# BusPirate-ultra-testboard_v1_0.net
KiCad netlist of a schematic drawn in EAGLE
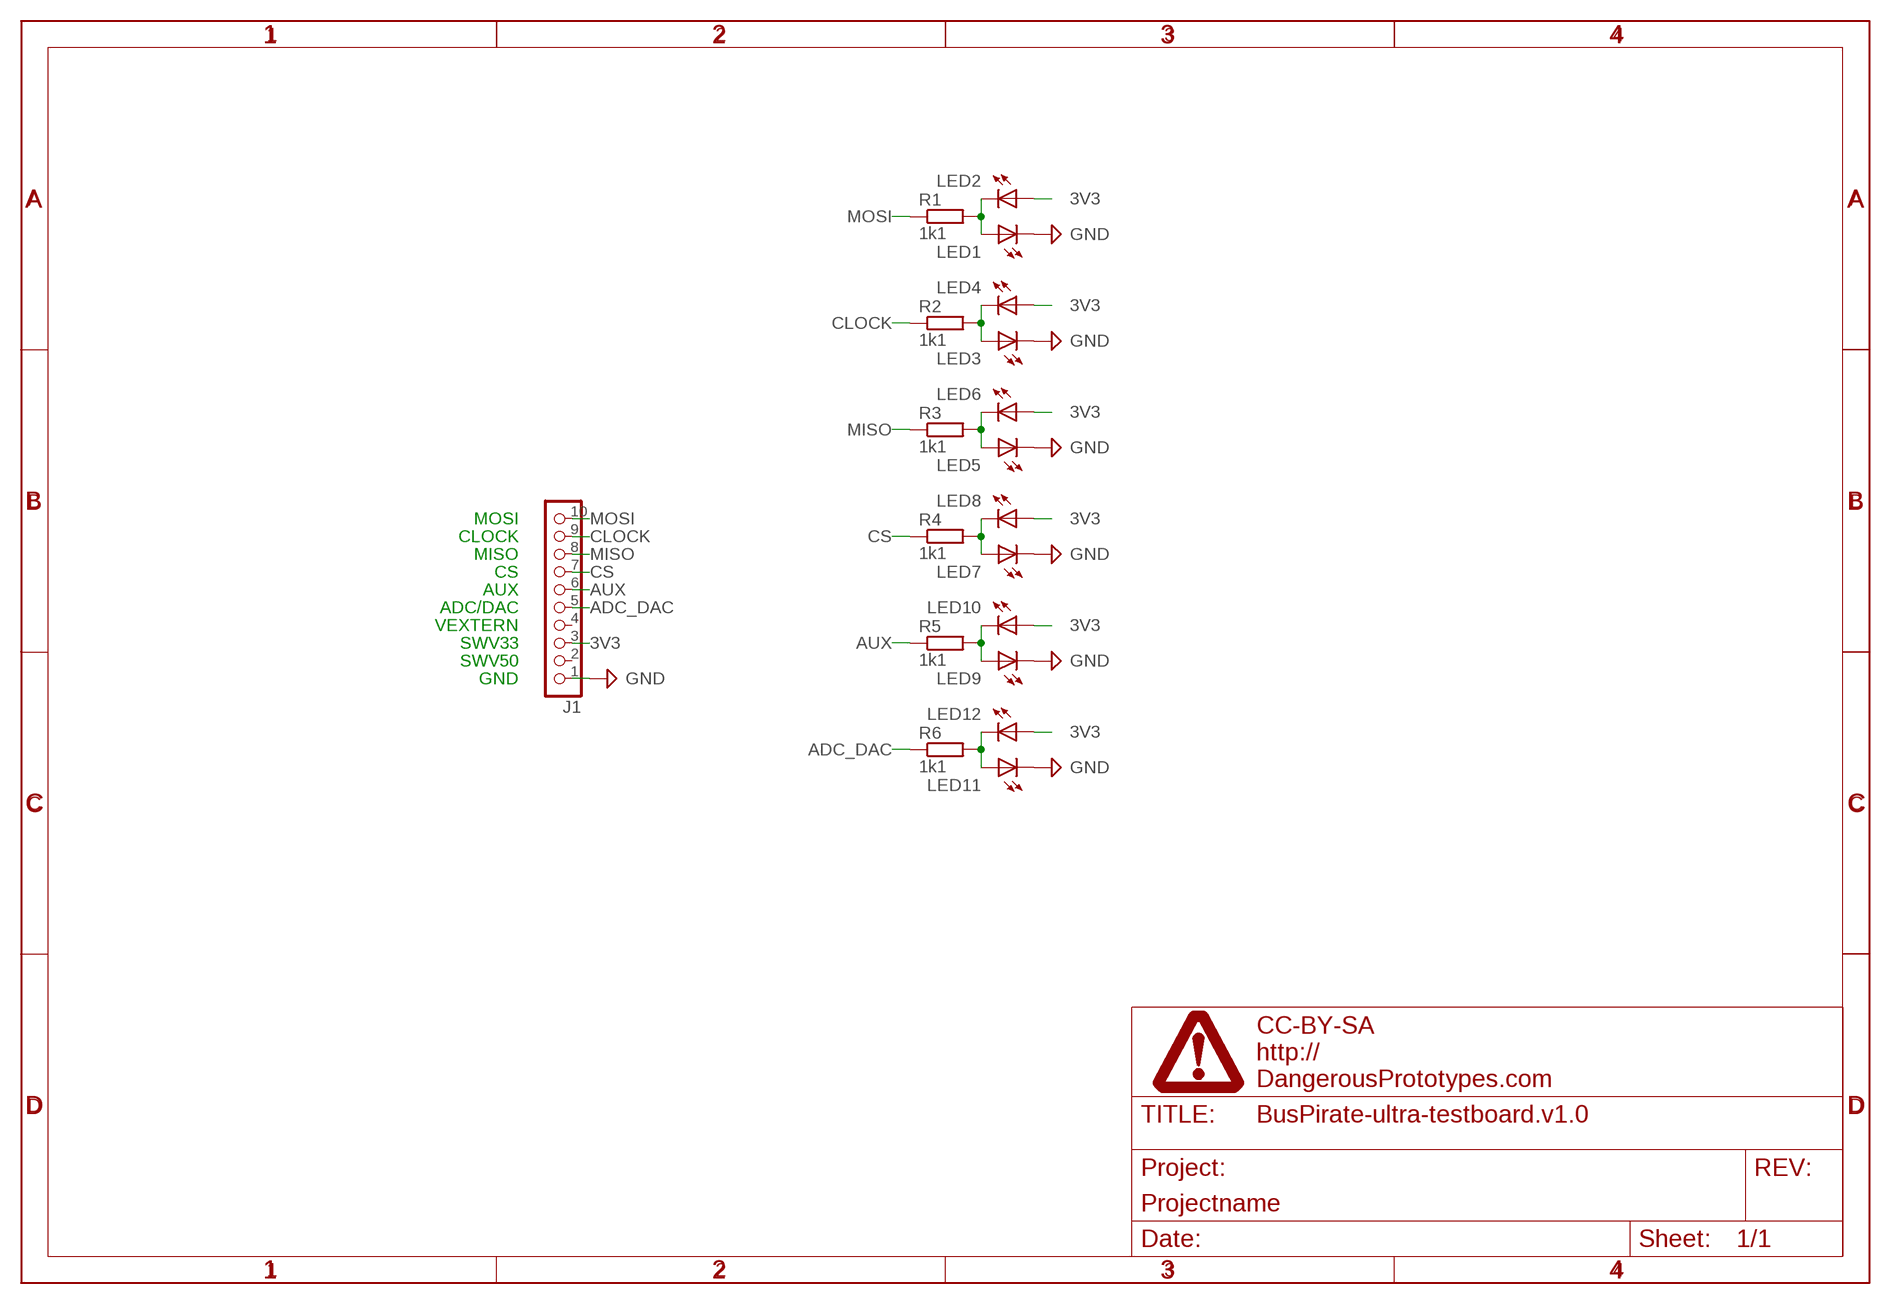
[diagram p0: schematic, sheet 1]

(export (version "E")
  (design (tool "Eeschema 10.0.6"))
  (components
    (comp (ref "J1")
      (value "CON_HEADER_1X10-RIGHT_ANGLED_PTH")
      (footprint "eagle-import:M1X10_FEMALE_RIGHT_ANGLED_PTH")
      (libsource (lib "eagle-import") (part "CON_HEADER_1X10-RIGHT_ANGLED_PTH"))
    )
    (comp (ref "LED1")
      (value "LED-0805")
      (footprint "eagle-import:LED-805")
      (libsource (lib "eagle-import") (part "LED-0805"))
    )
    (comp (ref "LED2")
      (value "LED-0805")
      (footprint "eagle-import:LED-805")
      (libsource (lib "eagle-import") (part "LED-0805"))
    )
    (comp (ref "LED3")
      (value "LED-0805")
      (footprint "eagle-import:LED-805")
      (libsource (lib "eagle-import") (part "LED-0805"))
    )
    (comp (ref "LED4")
      (value "LED-0805")
      (footprint "eagle-import:LED-805")
      (libsource (lib "eagle-import") (part "LED-0805"))
    )
    (comp (ref "LED5")
      (value "LED-0805")
      (footprint "eagle-import:LED-805")
      (libsource (lib "eagle-import") (part "LED-0805"))
    )
    (comp (ref "LED6")
      (value "LED-0805")
      (footprint "eagle-import:LED-805")
      (libsource (lib "eagle-import") (part "LED-0805"))
    )
    (comp (ref "LED7")
      (value "LED-0805")
      (footprint "eagle-import:LED-805")
      (libsource (lib "eagle-import") (part "LED-0805"))
    )
    (comp (ref "LED8")
      (value "LED-0805")
      (footprint "eagle-import:LED-805")
      (libsource (lib "eagle-import") (part "LED-0805"))
    )
    (comp (ref "LED9")
      (value "LED-0805")
      (footprint "eagle-import:LED-805")
      (libsource (lib "eagle-import") (part "LED-0805"))
    )
    (comp (ref "LED10")
      (value "LED-0805")
      (footprint "eagle-import:LED-805")
      (libsource (lib "eagle-import") (part "LED-0805"))
    )
    (comp (ref "LED11")
      (value "LED-0805")
      (footprint "eagle-import:LED-805")
      (libsource (lib "eagle-import") (part "LED-0805"))
    )
    (comp (ref "LED12")
      (value "LED-0805")
      (footprint "eagle-import:LED-805")
      (libsource (lib "eagle-import") (part "LED-0805"))
    )
    (comp (ref "PAGE1")
      (value "FRAME_DINA4_L")
      (footprint "eagle-import:DP_LOGO")
      (libsource (lib "eagle-import") (part "FRAME_DINA4_L"))
    )
    (comp (ref "R1")
      (value "1k1")
      (footprint "eagle-import:R603")
      (libsource (lib "eagle-import") (part "RESISTOR-0603"))
    )
    (comp (ref "R2")
      (value "1k1")
      (footprint "eagle-import:R603")
      (libsource (lib "eagle-import") (part "RESISTOR-0603"))
    )
    (comp (ref "R3")
      (value "1k1")
      (footprint "eagle-import:R603")
      (libsource (lib "eagle-import") (part "RESISTOR-0603"))
    )
    (comp (ref "R4")
      (value "1k1")
      (footprint "eagle-import:R603")
      (libsource (lib "eagle-import") (part "RESISTOR-0603"))
    )
    (comp (ref "R5")
      (value "1k1")
      (footprint "eagle-import:R603")
      (libsource (lib "eagle-import") (part "RESISTOR-0603"))
    )
    (comp (ref "R6")
      (value "1k1")
      (footprint "eagle-import:R603")
      (libsource (lib "eagle-import") (part "RESISTOR-0603"))
    )
  )
  (nets
    (net (code "1") (name "/3V3") (class "Default")
      (node (ref "J1") (pin "3") (pinfunction "3_3") (pintype "passive"))
      (node (ref "LED10") (pin "A") (pinfunction "A_A") (pintype "passive"))
      (node (ref "LED12") (pin "A") (pinfunction "A_A") (pintype "passive"))
      (node (ref "LED2") (pin "A") (pinfunction "A_A") (pintype "passive"))
      (node (ref "LED4") (pin "A") (pinfunction "A_A") (pintype "passive"))
      (node (ref "LED6") (pin "A") (pinfunction "A_A") (pintype "passive"))
      (node (ref "LED8") (pin "A") (pinfunction "A_A") (pintype "passive"))
    )
    (net (code "2") (name "/ADC_DAC") (class "Default")
      (node (ref "J1") (pin "5") (pinfunction "5_5") (pintype "passive"))
      (node (ref "R6") (pin "1") (pinfunction "1_1") (pintype "passive"))
    )
    (net (code "3") (name "/AUX") (class "Default")
      (node (ref "J1") (pin "6") (pinfunction "6_6") (pintype "passive"))
      (node (ref "R5") (pin "1") (pinfunction "1_1") (pintype "passive"))
    )
    (net (code "4") (name "/CLOCK") (class "Default")
      (node (ref "J1") (pin "9") (pinfunction "9_9") (pintype "passive"))
      (node (ref "R2") (pin "1") (pinfunction "1_1") (pintype "passive"))
    )
    (net (code "5") (name "/CS") (class "Default")
      (node (ref "J1") (pin "7") (pinfunction "7_7") (pintype "passive"))
      (node (ref "R4") (pin "1") (pinfunction "1_1") (pintype "passive"))
    )
    (net (code "6") (name "/MISO") (class "Default")
      (node (ref "J1") (pin "8") (pinfunction "8_8") (pintype "passive"))
      (node (ref "R3") (pin "1") (pinfunction "1_1") (pintype "passive"))
    )
    (net (code "7") (name "/MOSI") (class "Default")
      (node (ref "J1") (pin "10") (pinfunction "10_10") (pintype "passive"))
      (node (ref "R1") (pin "1") (pinfunction "1_1") (pintype "passive"))
    )
    (net (code "8") (name "DGND") (class "Default")
      (node (ref "J1") (pin "1") (pinfunction "1_1") (pintype "passive"))
      (node (ref "LED1") (pin "C") (pinfunction "C_C") (pintype "passive"))
      (node (ref "LED11") (pin "C") (pinfunction "C_C") (pintype "passive"))
      (node (ref "LED3") (pin "C") (pinfunction "C_C") (pintype "passive"))
      (node (ref "LED5") (pin "C") (pinfunction "C_C") (pintype "passive"))
      (node (ref "LED7") (pin "C") (pinfunction "C_C") (pintype "passive"))
      (node (ref "LED9") (pin "C") (pinfunction "C_C") (pintype "passive"))
    )
    (net (code "9") (name "Net-(LED1-PadA)") (class "Default")
      (node (ref "LED1") (pin "A") (pinfunction "A_A") (pintype "passive"))
      (node (ref "LED2") (pin "C") (pinfunction "C_C") (pintype "passive"))
      (node (ref "R1") (pin "2") (pinfunction "2_2") (pintype "passive"))
    )
    (net (code "10") (name "Net-(LED3-PadA)") (class "Default")
      (node (ref "LED3") (pin "A") (pinfunction "A_A") (pintype "passive"))
      (node (ref "LED4") (pin "C") (pinfunction "C_C") (pintype "passive"))
      (node (ref "R2") (pin "2") (pinfunction "2_2") (pintype "passive"))
    )
    (net (code "11") (name "Net-(LED5-PadA)") (class "Default")
      (node (ref "LED5") (pin "A") (pinfunction "A_A") (pintype "passive"))
      (node (ref "LED6") (pin "C") (pinfunction "C_C") (pintype "passive"))
      (node (ref "R3") (pin "2") (pinfunction "2_2") (pintype "passive"))
    )
    (net (code "12") (name "Net-(LED7-PadA)") (class "Default")
      (node (ref "LED7") (pin "A") (pinfunction "A_A") (pintype "passive"))
      (node (ref "LED8") (pin "C") (pinfunction "C_C") (pintype "passive"))
      (node (ref "R4") (pin "2") (pinfunction "2_2") (pintype "passive"))
    )
    (net (code "13") (name "Net-(LED10-PadC)") (class "Default")
      (node (ref "LED10") (pin "C") (pinfunction "C_C") (pintype "passive"))
      (node (ref "LED9") (pin "A") (pinfunction "A_A") (pintype "passive"))
      (node (ref "R5") (pin "2") (pinfunction "2_2") (pintype "passive"))
    )
    (net (code "14") (name "Net-(LED11-PadA)") (class "Default")
      (node (ref "LED11") (pin "A") (pinfunction "A_A") (pintype "passive"))
      (node (ref "LED12") (pin "C") (pinfunction "C_C") (pintype "passive"))
      (node (ref "R6") (pin "2") (pinfunction "2_2") (pintype "passive"))
    )
    (net (code "15") (name "unconnected-(J1-Pad2)") (class "Default")
      (node (ref "J1") (pin "2") (pinfunction "2_2") (pintype "passive"))
    )
    (net (code "16") (name "unconnected-(J1-Pad4)") (class "Default")
      (node (ref "J1") (pin "4") (pinfunction "4_4") (pintype "passive"))
    )
  )
)
